# RGBWW-003.net
KiCad netlist of a schematic drawn in EAGLE
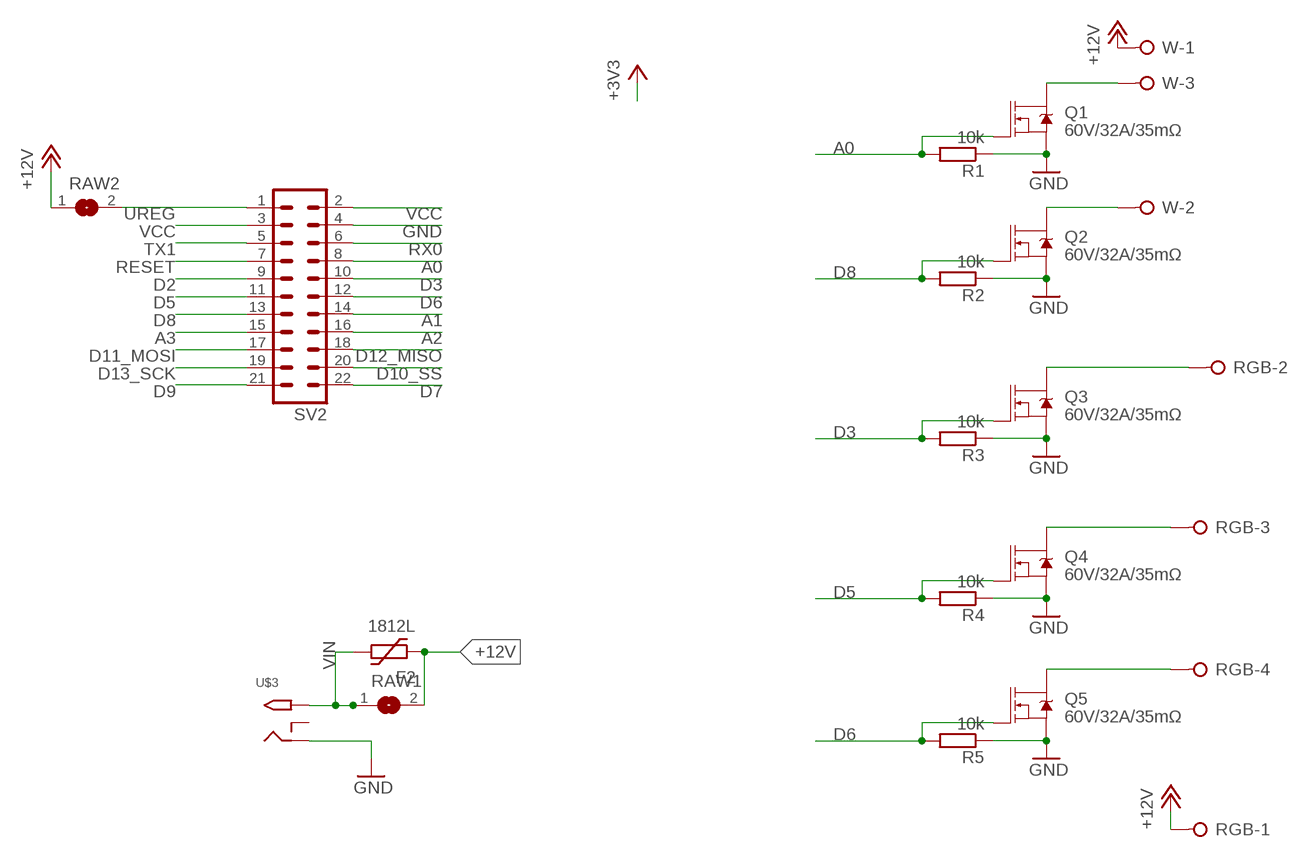
[diagram p0: schematic, sheet 1]

(export (version "E")
  (design (tool "Eeschema 10.0.6"))
  (components
    (comp (ref "F2")
      (value "1812L")
      (footprint "eagle-import:1812L")
      (libsource (lib "eagle-import") (part "1812L"))
    )
    (comp (ref "Q1")
      (value "60V/32A/35mΩ")
      (footprint "eagle-import:TO220V")
      (libsource (lib "eagle-import") (part "MOSFET-NCH-FQP30N06L"))
    )
    (comp (ref "Q2")
      (value "60V/32A/35mΩ")
      (footprint "eagle-import:TO220V")
      (libsource (lib "eagle-import") (part "MOSFET-NCH-FQP30N06L"))
    )
    (comp (ref "Q3")
      (value "60V/32A/35mΩ")
      (footprint "eagle-import:TO220V")
      (libsource (lib "eagle-import") (part "MOSFET-NCH-FQP30N06L"))
    )
    (comp (ref "Q4")
      (value "60V/32A/35mΩ")
      (footprint "eagle-import:TO220V")
      (libsource (lib "eagle-import") (part "MOSFET-NCH-FQP30N06L"))
    )
    (comp (ref "Q5")
      (value "60V/32A/35mΩ")
      (footprint "eagle-import:TO220V")
      (libsource (lib "eagle-import") (part "MOSFET-NCH-FQP30N06L"))
    )
    (comp (ref "R1")
      (value "10k")
      (footprint "eagle-import:R0805")
      (libsource (lib "eagle-import") (part "R-EU_R0805"))
    )
    (comp (ref "R2")
      (value "10k")
      (footprint "eagle-import:R0805")
      (libsource (lib "eagle-import") (part "R-EU_R0805"))
    )
    (comp (ref "R3")
      (value "10k")
      (footprint "eagle-import:R0805")
      (libsource (lib "eagle-import") (part "R-EU_R0805"))
    )
    (comp (ref "R4")
      (value "10k")
      (footprint "eagle-import:R0805")
      (libsource (lib "eagle-import") (part "R-EU_R0805"))
    )
    (comp (ref "R5")
      (value "10k")
      (footprint "eagle-import:R0805")
      (libsource (lib "eagle-import") (part "R-EU_R0805"))
    )
    (comp (ref "RAW1")
      (value "SJ")
      (footprint "eagle-import:SJ")
      (libsource (lib "eagle-import") (part "SJ"))
    )
    (comp (ref "RAW2")
      (value "SJ")
      (footprint "eagle-import:SJ")
      (libsource (lib "eagle-import") (part "SJ"))
    )
    (comp (ref "RGB")
      (value "W237-04P")
      (footprint "eagle-import:W237-4P")
      (libsource (lib "eagle-import") (part "W237-04P"))
    )
    (comp (ref "SV2")
      (value "MA11-2")
      (footprint "eagle-import:MA11-2")
      (libsource (lib "eagle-import") (part "MA11-2"))
    )
    (comp (ref "U$3")
      (value "2.1MMJACKTHM")
      (footprint "eagle-import:PJ-102A")
      (libsource (lib "eagle-import") (part "2.1MMJACKTHM"))
    )
    (comp (ref "W")
      (value "W237-03P")
      (footprint "eagle-import:W237-133")
      (libsource (lib "eagle-import") (part "W237-03P"))
    )
  )
  (nets
    (net (code "2") (name "+12V") (class "Default")
      (node (ref "F2") (pin "P$1") (pinfunction "1_P$1") (pintype "passive"))
      (node (ref "RAW1") (pin "2") (pinfunction "2_2") (pintype "passive"))
      (node (ref "RAW2") (pin "1") (pinfunction "1_1") (pintype "passive"))
      (node (ref "RGB") (pin "1") (pinfunction "KL_1") (pintype "passive"))
      (node (ref "W") (pin "1") (pinfunction "KL_1") (pintype "passive"))
    )
    (net (code "3") (name "/A0") (class "Default")
      (node (ref "Q1") (pin "1") (pinfunction "G_1") (pintype "bidirectional"))
      (node (ref "R1") (pin "2") (pinfunction "2_2") (pintype "passive"))
      (node (ref "SV2") (pin "8") (pinfunction "8_8") (pintype "passive"))
    )
    (net (code "4") (name "/A1") (class "Default")
      (node (ref "SV2") (pin "14") (pinfunction "14_14") (pintype "passive"))
    )
    (net (code "5") (name "/A2") (class "Default")
      (node (ref "SV2") (pin "16") (pinfunction "16_16") (pintype "passive"))
    )
    (net (code "6") (name "/A3") (class "Default")
      (node (ref "SV2") (pin "15") (pinfunction "15_15") (pintype "passive"))
    )
    (net (code "7") (name "/D2") (class "Default")
      (node (ref "SV2") (pin "9") (pinfunction "9_9") (pintype "passive"))
    )
    (net (code "8") (name "/D3") (class "Default")
      (node (ref "Q3") (pin "1") (pinfunction "G_1") (pintype "bidirectional"))
      (node (ref "R3") (pin "2") (pinfunction "2_2") (pintype "passive"))
      (node (ref "SV2") (pin "10") (pinfunction "10_10") (pintype "passive"))
    )
    (net (code "9") (name "/D5") (class "Default")
      (node (ref "Q4") (pin "1") (pinfunction "G_1") (pintype "bidirectional"))
      (node (ref "R4") (pin "2") (pinfunction "2_2") (pintype "passive"))
      (node (ref "SV2") (pin "11") (pinfunction "11_11") (pintype "passive"))
    )
    (net (code "10") (name "/D6") (class "Default")
      (node (ref "Q5") (pin "1") (pinfunction "G_1") (pintype "bidirectional"))
      (node (ref "R5") (pin "2") (pinfunction "2_2") (pintype "passive"))
      (node (ref "SV2") (pin "12") (pinfunction "12_12") (pintype "passive"))
    )
    (net (code "11") (name "/D7") (class "Default")
      (node (ref "SV2") (pin "22") (pinfunction "22_22") (pintype "passive"))
    )
    (net (code "12") (name "/D8") (class "Default")
      (node (ref "Q2") (pin "1") (pinfunction "G_1") (pintype "bidirectional"))
      (node (ref "R2") (pin "2") (pinfunction "2_2") (pintype "passive"))
      (node (ref "SV2") (pin "13") (pinfunction "13_13") (pintype "passive"))
    )
    (net (code "13") (name "/D9") (class "Default")
      (node (ref "SV2") (pin "21") (pinfunction "21_21") (pintype "passive"))
    )
    (net (code "14") (name "/D10_SS") (class "Default")
      (node (ref "SV2") (pin "20") (pinfunction "20_20") (pintype "passive"))
    )
    (net (code "15") (name "/D11_MOSI") (class "Default")
      (node (ref "SV2") (pin "17") (pinfunction "17_17") (pintype "passive"))
    )
    (net (code "16") (name "/D12_MISO") (class "Default")
      (node (ref "SV2") (pin "18") (pinfunction "18_18") (pintype "passive"))
    )
    (net (code "17") (name "/D13_SCK") (class "Default")
      (node (ref "SV2") (pin "19") (pinfunction "19_19") (pintype "passive"))
    )
    (net (code "18") (name "/RESET") (class "Default")
      (node (ref "SV2") (pin "7") (pinfunction "7_7") (pintype "passive"))
    )
    (net (code "19") (name "/RX0") (class "Default")
      (node (ref "SV2") (pin "6") (pinfunction "6_6") (pintype "passive"))
    )
    (net (code "20") (name "/TX1") (class "Default")
      (node (ref "SV2") (pin "5") (pinfunction "5_5") (pintype "passive"))
    )
    (net (code "21") (name "/UREG") (class "Default")
      (node (ref "RAW2") (pin "2") (pinfunction "2_2") (pintype "passive"))
      (node (ref "SV2") (pin "1") (pinfunction "1_1") (pintype "passive"))
    )
    (net (code "22") (name "/VCC") (class "Default")
      (node (ref "SV2") (pin "2") (pinfunction "2_2") (pintype "passive"))
      (node (ref "SV2") (pin "3") (pinfunction "3_3") (pintype "passive"))
    )
    (net (code "23") (name "/VIN") (class "Default")
      (node (ref "F2") (pin "P$2") (pinfunction "2_P$2") (pintype "passive"))
      (node (ref "RAW1") (pin "1") (pinfunction "1_1") (pintype "passive"))
      (node (ref "U$3") (pin "TIP") (pinfunction "TIP_TIP") (pintype "bidirectional"))
    )
    (net (code "24") (name "GND") (class "Default")
      (node (ref "Q1") (pin "3") (pinfunction "S_3") (pintype "bidirectional"))
      (node (ref "Q2") (pin "3") (pinfunction "S_3") (pintype "bidirectional"))
      (node (ref "Q3") (pin "3") (pinfunction "S_3") (pintype "bidirectional"))
      (node (ref "Q4") (pin "3") (pinfunction "S_3") (pintype "bidirectional"))
      (node (ref "Q5") (pin "3") (pinfunction "S_3") (pintype "bidirectional"))
      (node (ref "R1") (pin "1") (pinfunction "1_1") (pintype "passive"))
      (node (ref "R2") (pin "1") (pinfunction "1_1") (pintype "passive"))
      (node (ref "R3") (pin "1") (pinfunction "1_1") (pintype "passive"))
      (node (ref "R4") (pin "1") (pinfunction "1_1") (pintype "passive"))
      (node (ref "R5") (pin "1") (pinfunction "1_1") (pintype "passive"))
      (node (ref "SV2") (pin "4") (pinfunction "4_4") (pintype "passive"))
      (node (ref "U$3") (pin "RING") (pinfunction "RING_RING") (pintype "bidirectional"))
    )
    (net (code "25") (name "Net-(Q1-D)") (class "Default")
      (node (ref "Q1") (pin "2") (pinfunction "D_2") (pintype "bidirectional"))
      (node (ref "W") (pin "3") (pinfunction "KL_3") (pintype "passive"))
    )
    (net (code "26") (name "Net-(Q2-D)") (class "Default")
      (node (ref "Q2") (pin "2") (pinfunction "D_2") (pintype "bidirectional"))
      (node (ref "W") (pin "2") (pinfunction "KL_2") (pintype "passive"))
    )
    (net (code "27") (name "Net-(Q3-D)") (class "Default")
      (node (ref "Q3") (pin "2") (pinfunction "D_2") (pintype "bidirectional"))
      (node (ref "RGB") (pin "2") (pinfunction "KL_2") (pintype "passive"))
    )
    (net (code "28") (name "Net-(Q4-D)") (class "Default")
      (node (ref "Q4") (pin "2") (pinfunction "D_2") (pintype "bidirectional"))
      (node (ref "RGB") (pin "3") (pinfunction "KL_3") (pintype "passive"))
    )
    (net (code "29") (name "Net-(Q5-D)") (class "Default")
      (node (ref "Q5") (pin "2") (pinfunction "D_2") (pintype "bidirectional"))
      (node (ref "RGB") (pin "4") (pinfunction "KL_4") (pintype "passive"))
    )
    (net (code "30") (name "unconnected-(U$3-PadRING_SW)") (class "Default")
      (node (ref "U$3") (pin "RING_SW") (pinfunction "RING_SW_RING_SW") (pintype "bidirectional"))
    )
  )
)
